# Flash.net
KiCad netlist of a schematic drawn in Altium Designer
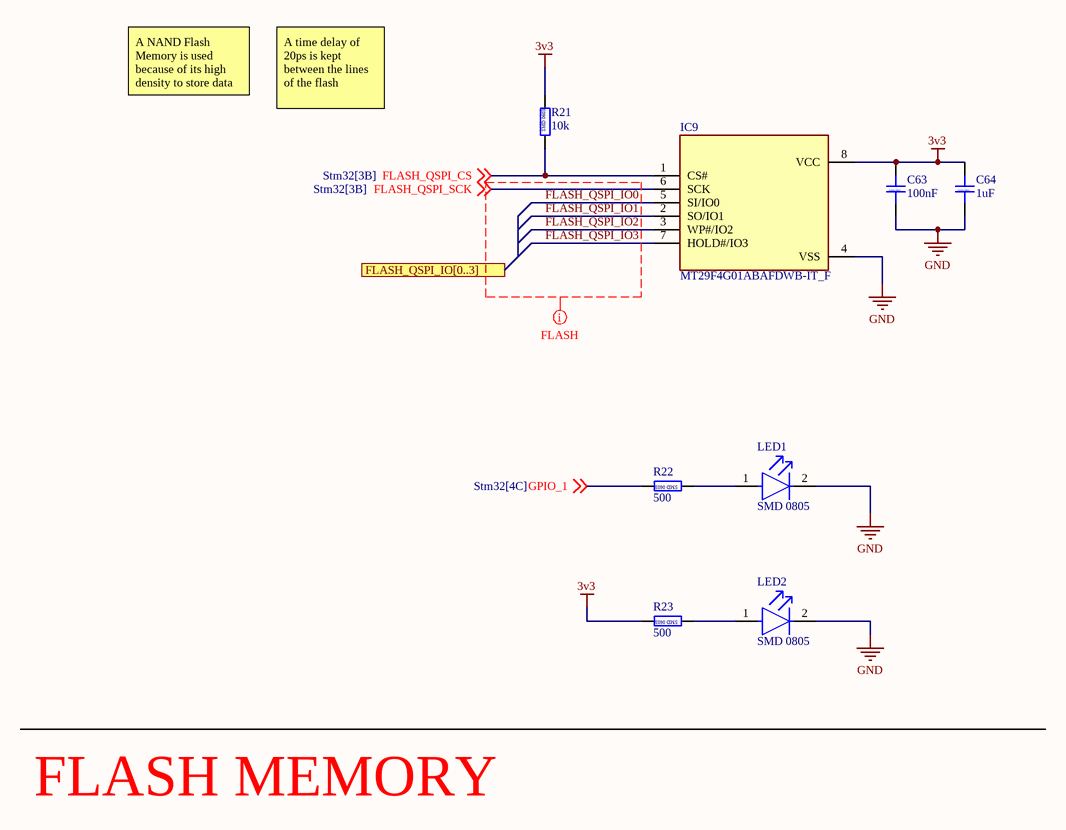
[diagram p0: Flash.SchDoc]

(export (version "E")
  (design (tool "Eeschema 10.0.6"))
  (components
    (comp (ref "C63")
      (value "100nF")
      (footprint "CAP_0603")
      (description "Capacitor SMD 0603 RATED")
      (libsource (lib "STeRG-Passives-Standard") (part "Capacitor-SMD-0603"))
    )
    (comp (ref "C64")
      (value "1uF")
      (footprint "CAP_0603")
      (description "Capacitor SMD 0603 RATED")
      (libsource (lib "STeRG-Passives-Standard") (part "Capacitor-SMD-0603"))
    )
    (comp (ref "IC9")
      (value "MT29F4G01ABAFDWB-IT_F")
      (footprint "SamacSys:SON127P800X600X65-8N")
      (description "Integrated Circuit")
      (fields
        (field (name "MANUFACTURER_PART_NUMBER") "MT29F4G01ABAFDWB-IT:F")
        (field (name "MOUSER PART NUMBER") "340-359563")
      )
      (libsource (lib "SamacSys") (part "MT29F4G01ABAFDWB-IT_F"))
    )
    (comp (ref "LED1")
      (value "SMD 0805")
      (footprint "FP-SM0805YCL-MFG")
      (description "LED YELLOW CLEAR 0805 SMD")
      (libsource (lib "Altium Content Vault") (part "ab1c01a81903e929fc6c44469aada92"))
    )
    (comp (ref "LED2")
      (value "SMD 0805")
      (footprint "FP-SM0805YCL-MFG")
      (description "LED YELLOW CLEAR 0805 SMD")
      (libsource (lib "Altium Content Vault") (part "ab1c01a81903e929fc6c44469aada92"))
    )
    (comp (ref "R21")
      (value "10k")
      (footprint "RES_0603")
      (description "Resistor SMD 0603 RATED")
      (libsource (lib "STeRG-Passives-Standard") (part "Resistor-SMD-0603"))
    )
    (comp (ref "R22")
      (value "500")
      (footprint "RES_0603")
      (description "Resistor SMD 0603 RATED")
      (libsource (lib "STeRG-Passives-Standard") (part "Resistor-SMD-0603"))
    )
    (comp (ref "R23")
      (value "500")
      (footprint "RES_0603")
      (description "Resistor SMD 0603 RATED")
      (libsource (lib "STeRG-Passives-Standard") (part "Resistor-SMD-0603"))
    )
  )
  (nets
    (net (code "1") (name "/FLASH_QSPI_IO0") (class "Default")
      (node (ref "IC9") (pin "5") (pinfunction "SI/IO0_5") (pintype "passive"))
    )
    (net (code "2") (name "/FLASH_QSPI_IO1") (class "Default")
      (node (ref "IC9") (pin "2") (pinfunction "SO/IO1_2") (pintype "passive"))
    )
    (net (code "3") (name "/FLASH_QSPI_IO2") (class "Default")
      (node (ref "IC9") (pin "3") (pinfunction "WP#/IO2_3") (pintype "passive"))
    )
    (net (code "4") (name "/FLASH_QSPI_IO3") (class "Default")
      (node (ref "IC9") (pin "7") (pinfunction "HOLD#/IO3_7") (pintype "passive"))
    )
    (net (code "6") (name "3v3") (class "Default")
      (node (ref "C63") (pin "2") (pinfunction "2_2") (pintype "passive"))
      (node (ref "C64") (pin "2") (pinfunction "2_2") (pintype "passive"))
      (node (ref "IC9") (pin "8") (pinfunction "VCC_8") (pintype "passive"))
      (node (ref "R21") (pin "2") (pinfunction "2_2") (pintype "passive"))
      (node (ref "R23") (pin "2") (pinfunction "2_2") (pintype "passive"))
    )
    (net (code "7") (name "FLASH_QSPI_CS") (class "Default")
      (node (ref "IC9") (pin "1") (pinfunction "CS#_1") (pintype "passive"))
      (node (ref "R21") (pin "1") (pinfunction "1_1") (pintype "passive"))
    )
    (net (code "8") (name "FLASH_QSPI_SCK") (class "Default")
      (node (ref "IC9") (pin "6") (pinfunction "SCK_6") (pintype "passive"))
    )
    (net (code "9") (name "GND") (class "Default")
      (node (ref "C63") (pin "1") (pinfunction "1_1") (pintype "passive"))
      (node (ref "C64") (pin "1") (pinfunction "1_1") (pintype "passive"))
      (node (ref "IC9") (pin "4") (pinfunction "VSS_4") (pintype "passive"))
      (node (ref "LED1") (pin "2") (pinfunction "C_2") (pintype "passive"))
      (node (ref "LED2") (pin "2") (pinfunction "C_2") (pintype "passive"))
    )
    (net (code "10") (name "GPIO_1") (class "Default")
      (node (ref "R22") (pin "2") (pinfunction "2_2") (pintype "passive"))
    )
    (net (code "11") (name "Net-(LED1-A)") (class "Default")
      (node (ref "LED1") (pin "1") (pinfunction "A_1") (pintype "passive"))
      (node (ref "R22") (pin "1") (pinfunction "1_1") (pintype "passive"))
    )
    (net (code "12") (name "Net-(LED2-A)") (class "Default")
      (node (ref "LED2") (pin "1") (pinfunction "A_1") (pintype "passive"))
      (node (ref "R23") (pin "1") (pinfunction "1_1") (pintype "passive"))
    )
  )
)
